# LaserProtection_Top_V10.net
KiCad netlist of a schematic drawn in Altium Designer
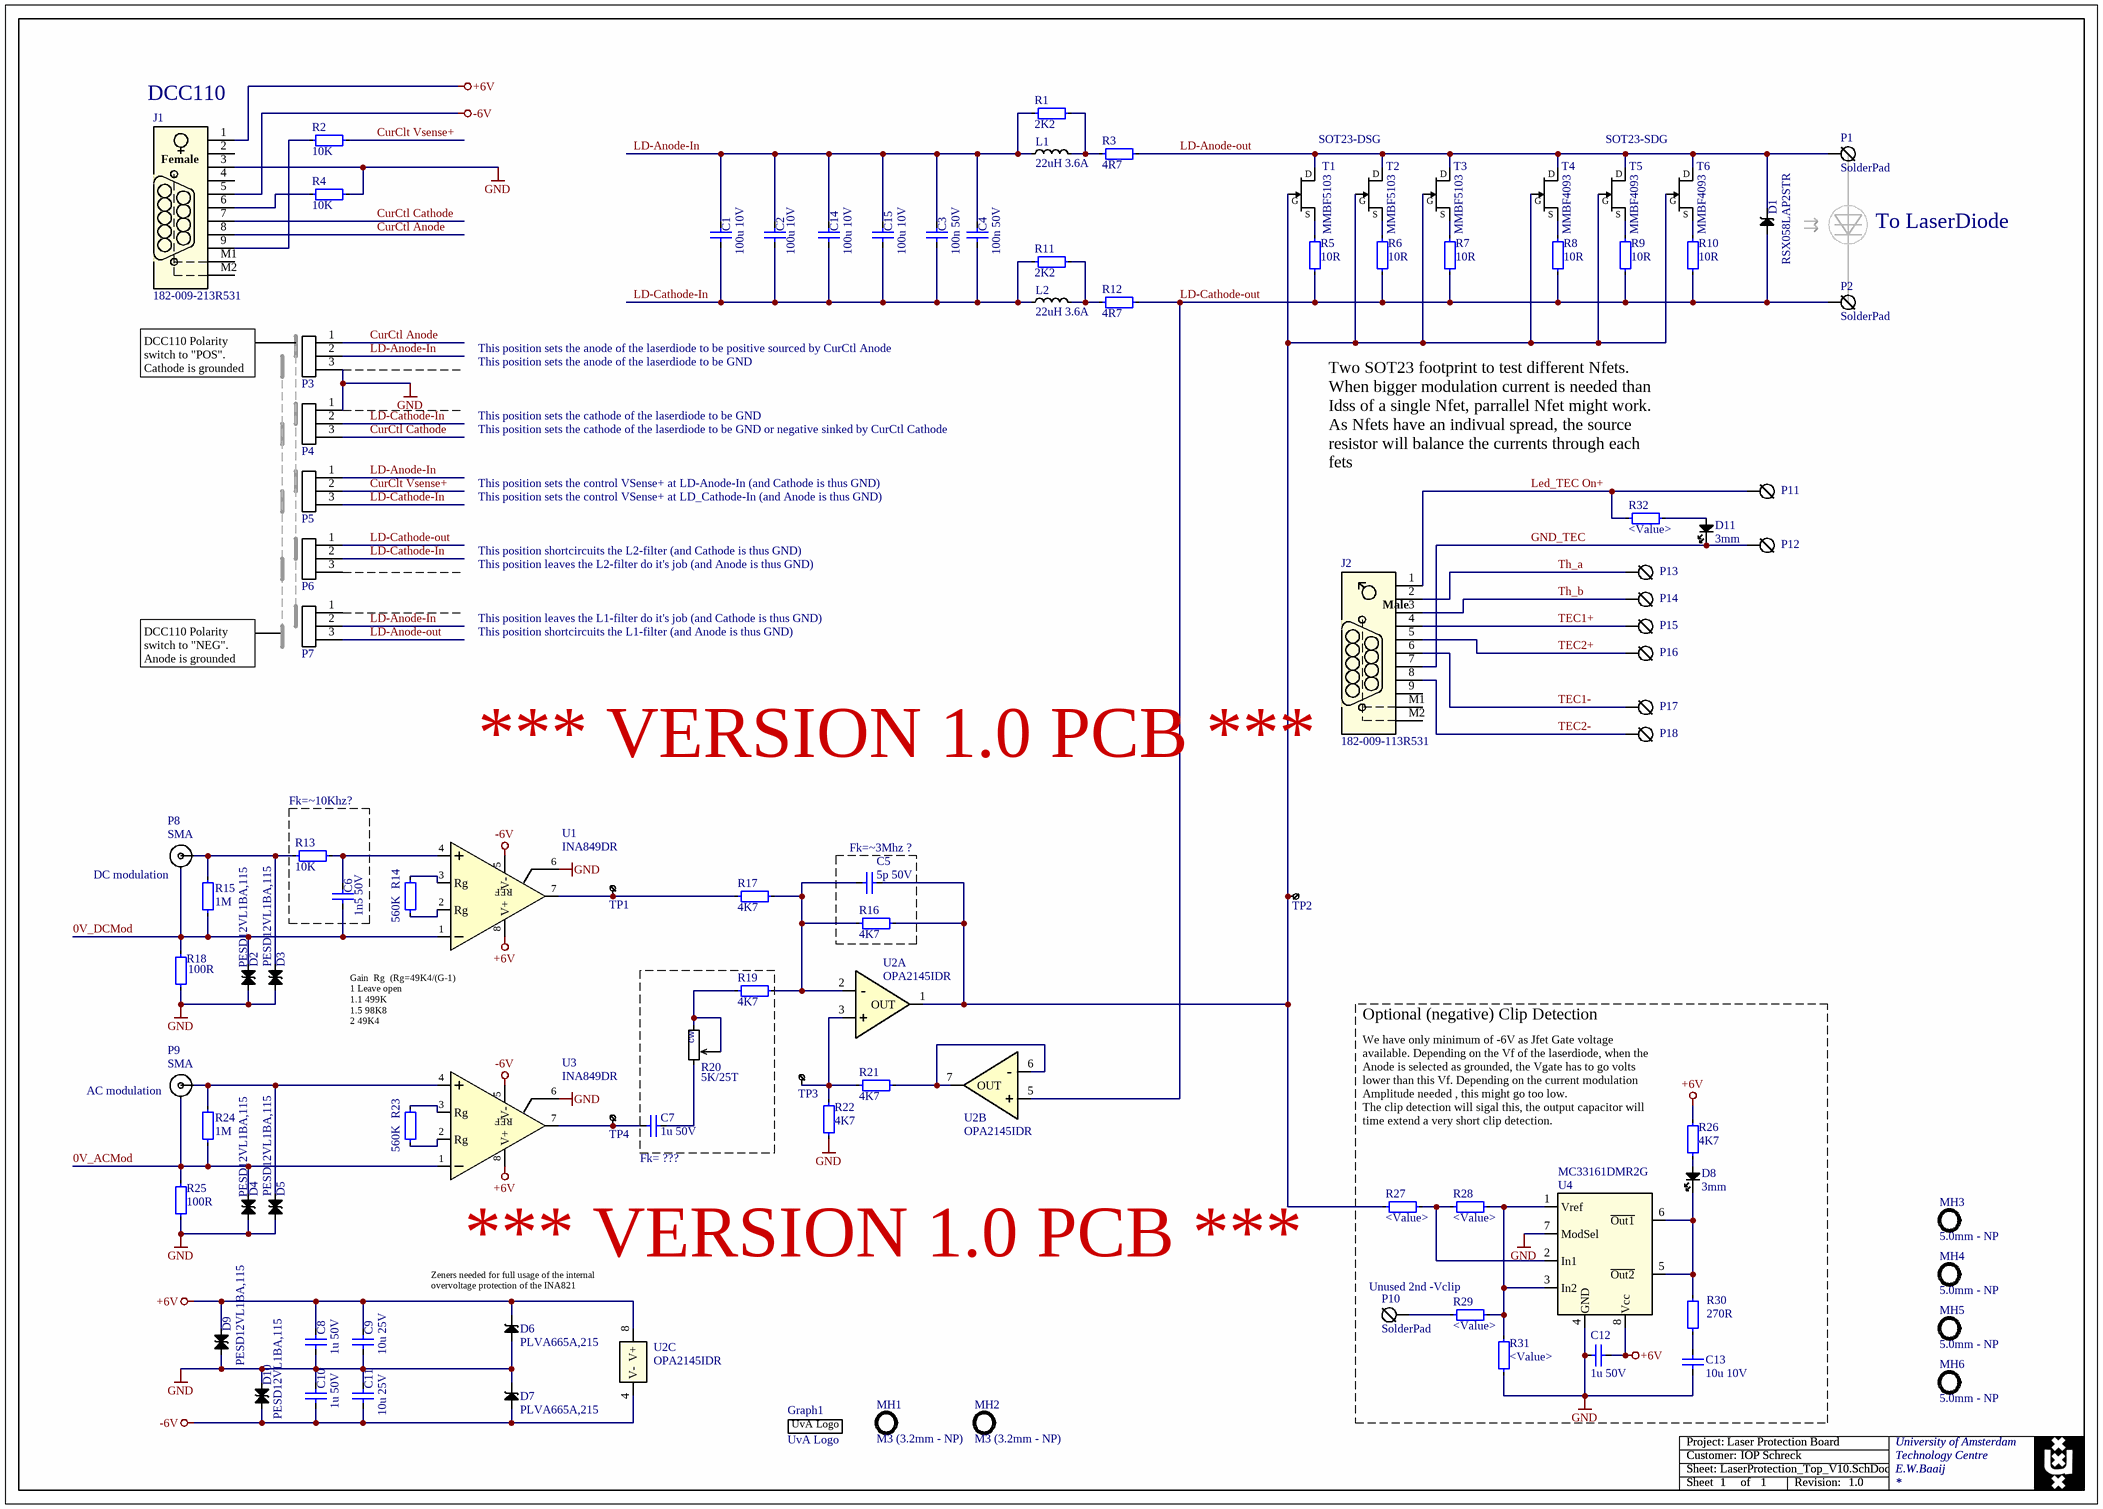
[diagram p0: LaserProtection_Top_V10.SchDoc]

(export (version "E")
  (design (tool "Eeschema 10.0.6"))
  (components
    (comp (ref "C1")
      (value "100u 10V")
      (footprint "cap1206MD")
      (description "MLCC 100 µF, 10 V, 1206 [3216 Metric], ± 20%, X5R")
      (fields
        (field (name "MANUFACTURER") "TDK")
        (field (name "AUTHOR") "EB")
        (field (name "CHECKED BY") "Unchecked")
      )
      (libsource (lib "TC_Parts") (part "capacitor"))
    )
    (comp (ref "C2")
      (value "100u 10V")
      (footprint "cap1206MD")
      (description "MLCC 100 µF, 10 V, 1206 [3216 Metric], ± 20%, X5R")
      (fields
        (field (name "MANUFACTURER") "TDK")
        (field (name "AUTHOR") "EB")
        (field (name "CHECKED BY") "Unchecked")
      )
      (libsource (lib "TC_Parts") (part "capacitor"))
    )
    (comp (ref "C3")
      (value "100n 50V")
      (footprint "cap0603MD")
      (fields
        (field (name "VOLTAGE") "50V")
        (field (name "AUTHOR") "TvR")
        (field (name "CHECKED BY") "Unchecked")
      )
      (libsource (lib "TC_Parts") (part "capacitor"))
    )
    (comp (ref "C4")
      (value "100n 50V")
      (footprint "cap0603MD")
      (fields
        (field (name "VOLTAGE") "50V")
        (field (name "AUTHOR") "TvR")
        (field (name "CHECKED BY") "Unchecked")
      )
      (libsource (lib "TC_Parts") (part "capacitor"))
    )
    (comp (ref "C5")
      (value "5p 50V")
      (footprint "cap0603MD")
      (fields
        (field (name "VOLTAGE") "50V")
        (field (name "AUTHOR") "Twe")
        (field (name "CHECKED BY") "Unchecked")
      )
      (libsource (lib "TC_Parts") (part "capacitor"))
    )
    (comp (ref "C6")
      (value "1n5 50V")
      (footprint "cap0603MD")
      (fields
        (field (name "VOLTAGE") "50V")
        (field (name "AUTHOR") "EB")
        (field (name "CHECKED BY") "Unchecked")
      )
      (libsource (lib "TC_Parts") (part "capacitor"))
    )
    (comp (ref "C7")
      (value "1u 50V")
      (footprint "cap0603MD")
      (fields
        (field (name "VOLTAGE") "50V")
        (field (name "AUTHOR") "Twe")
        (field (name "CHECKED BY") "Unchecked")
      )
      (libsource (lib "TC_Parts") (part "capacitor"))
    )
    (comp (ref "C8")
      (value "1u 50V")
      (footprint "cap0603MD")
      (fields
        (field (name "VOLTAGE") "50V")
        (field (name "AUTHOR") "Twe")
        (field (name "CHECKED BY") "Unchecked")
      )
      (libsource (lib "TC_Parts") (part "capacitor"))
    )
    (comp (ref "C9")
      (value "10u 25V")
      (footprint "cap0805MD")
      (fields
        (field (name "VOLTAGE") "25V")
        (field (name "AUTHOR") "EB")
        (field (name "CHECKED BY") "Unchecked")
      )
      (libsource (lib "TC_Parts") (part "capacitor"))
    )
    (comp (ref "C10")
      (value "1u 50V")
      (footprint "cap0603MD")
      (fields
        (field (name "VOLTAGE") "50V")
        (field (name "AUTHOR") "Twe")
        (field (name "CHECKED BY") "Unchecked")
      )
      (libsource (lib "TC_Parts") (part "capacitor"))
    )
    (comp (ref "C11")
      (value "10u 25V")
      (footprint "cap0805MD")
      (fields
        (field (name "VOLTAGE") "25V")
        (field (name "AUTHOR") "EB")
        (field (name "CHECKED BY") "Unchecked")
      )
      (libsource (lib "TC_Parts") (part "capacitor"))
    )
    (comp (ref "C12")
      (value "1u 50V")
      (footprint "cap0603MD")
      (fields
        (field (name "VOLTAGE") "50V")
        (field (name "AUTHOR") "Twe")
        (field (name "CHECKED BY") "Unchecked")
      )
      (libsource (lib "TC_Parts") (part "capacitor"))
    )
    (comp (ref "C13")
      (value "10u 10V")
      (footprint "cap0603MD")
      (fields
        (field (name "VOLTAGE") "10V")
        (field (name "AUTHOR") "EB")
        (field (name "CHECKED BY") "Unchecked")
      )
      (libsource (lib "TC_Parts") (part "capacitor"))
    )
    (comp (ref "C14")
      (value "100u 10V")
      (footprint "cap1206MD")
      (description "MLCC 100 µF, 10 V, 1206 [3216 Metric], ± 20%, X5R")
      (fields
        (field (name "MANUFACTURER") "TDK")
        (field (name "AUTHOR") "EB")
        (field (name "CHECKED BY") "Unchecked")
      )
      (libsource (lib "TC_Parts") (part "capacitor"))
    )
    (comp (ref "C15")
      (value "100u 10V")
      (footprint "cap1206MD")
      (description "MLCC 100 µF, 10 V, 1206 [3216 Metric], ± 20%, X5R")
      (fields
        (field (name "MANUFACTURER") "TDK")
        (field (name "AUTHOR") "EB")
        (field (name "CHECKED BY") "Unchecked")
      )
      (libsource (lib "TC_Parts") (part "capacitor"))
    )
    (comp (ref "D1")
      (value "RSX058LAP2STR")
      (footprint "SODFL470X110-2N")
      (description "Schottky Diode, 3A, 200V, Vf=0.84 (3A/35C), Ir=5-100nA")
      (fields
        (field (name "MANUFACTURER") "ROHM")
        (field (name "AUTHOR") "EB")
        (field (name "CHECKED BY") "Unchecked")
      )
      (libsource (lib "TC_Parts") (part "DIODEZENER_CA"))
    )
    (comp (ref "D2")
      (value "PESD12VL1BA,115")
      (footprint "SOD-323-2-NoPol")
      (description "TVS Diode, Bidirectional, 12V, SOD-323, 2 Pins")
      (fields
        (field (name "MANUFACTURER") "Nexperia")
        (field (name "AUTHOR") "EB")
        (field (name "CHECKED BY") "Unchecked")
      )
      (libsource (lib "TC_Parts") (part "diodeSuppressor"))
    )
    (comp (ref "D3")
      (value "PESD12VL1BA,115")
      (footprint "SOD-323-2-NoPol")
      (description "TVS Diode, Bidirectional, 12V, SOD-323, 2 Pins")
      (fields
        (field (name "MANUFACTURER") "Nexperia")
        (field (name "AUTHOR") "EB")
        (field (name "CHECKED BY") "Unchecked")
      )
      (libsource (lib "TC_Parts") (part "diodeSuppressor"))
    )
    (comp (ref "D4")
      (value "PESD12VL1BA,115")
      (footprint "SOD-323-2-NoPol")
      (description "TVS Diode, Bidirectional, 12V, SOD-323, 2 Pins")
      (fields
        (field (name "MANUFACTURER") "Nexperia")
        (field (name "AUTHOR") "EB")
        (field (name "CHECKED BY") "Unchecked")
      )
      (libsource (lib "TC_Parts") (part "diodeSuppressor"))
    )
    (comp (ref "D5")
      (value "PESD12VL1BA,115")
      (footprint "SOD-323-2-NoPol")
      (description "TVS Diode, Bidirectional, 12V, SOD-323, 2 Pins")
      (fields
        (field (name "MANUFACTURER") "Nexperia")
        (field (name "AUTHOR") "EB")
        (field (name "CHECKED BY") "Unchecked")
      )
      (libsource (lib "TC_Parts") (part "diodeSuppressor"))
    )
    (comp (ref "D6")
      (value "PLVA665A,215")
      (footprint "SOT95P230X110-3N")
      (description "Zener 6v5, 250mW, 3%, SOT-23")
      (fields
        (field (name "MANUFACTURER") "Rohm")
        (field (name "AUTHOR") "EB")
        (field (name "CHECKED BY") "Unchecked")
      )
      (libsource (lib "TC_Parts") (part "DIODEZENER_AxC"))
    )
    (comp (ref "D7")
      (value "PLVA665A,215")
      (footprint "SOT95P230X110-3N")
      (description "Zener 6v5, 250mW, 3%, SOT-23")
      (fields
        (field (name "MANUFACTURER") "Rohm")
        (field (name "AUTHOR") "EB")
        (field (name "CHECKED BY") "Unchecked")
      )
      (libsource (lib "TC_Parts") (part "DIODEZENER_AxC"))
    )
    (comp (ref "D8")
      (value "3mm")
      (footprint "LED_3mm")
      (description "Generic 3mm LED Footprint")
      (fields
        (field (name "MANUFACTURER") "Wurth")
        (field (name "AUTHOR") "EB")
        (field (name "CHECKED BY") "Unchecked")
      )
      (libsource (lib "TC_Parts") (part "LED_CA"))
    )
    (comp (ref "D9")
      (value "PESD12VL1BA,115")
      (footprint "SOD-323-2-NoPol")
      (description "TVS Diode, Bidirectional, 12V, SOD-323, 2 Pins")
      (fields
        (field (name "MANUFACTURER") "Nexperia")
        (field (name "AUTHOR") "EB")
        (field (name "CHECKED BY") "Unchecked")
      )
      (libsource (lib "TC_Parts") (part "diodeSuppressor"))
    )
    (comp (ref "D10")
      (value "PESD12VL1BA,115")
      (footprint "SOD-323-2-NoPol")
      (description "TVS Diode, Bidirectional, 12V, SOD-323, 2 Pins")
      (fields
        (field (name "MANUFACTURER") "Nexperia")
        (field (name "AUTHOR") "EB")
        (field (name "CHECKED BY") "Unchecked")
      )
      (libsource (lib "TC_Parts") (part "diodeSuppressor"))
    )
    (comp (ref "D11")
      (value "3mm")
      (footprint "LED_3mm")
      (description "Generic 3mm LED Footprint")
      (fields
        (field (name "MANUFACTURER") "Wurth")
        (field (name "AUTHOR") "EB")
        (field (name "CHECKED BY") "Unchecked")
      )
      (libsource (lib "TC_Parts") (part "LED_CA"))
    )
    (comp (ref "Graph1")
      (value "UvA Logo")
      (footprint "UVA_LOGO_SMALL_HOR")
      (description "University of Amsterdam Logo")
      (fields (field (name "AUTHOR") "EB") (field (name "CHECKED BY") "PCB"))
      (libsource (lib "TC_Parts") (part "UvA_Logo"))
    )
    (comp (ref "J1")
      (value "182-009-213R531")
      (footprint "182-009-213Ryy1")
      (description "NorComp, D-SUB, 9 pins, Female, right angled PCB")
      (fields
        (field (name "MANUFACTURER") "NorComp")
        (field (name "AUTHOR") "EB")
        (field (name "CHECKED BY") "Unchecked")
      )
      (libsource (lib "TC_Parts") (part "D-SUB_9p_Female_PCB"))
    )
    (comp (ref "J2")
      (value "182-009-113R531")
      (footprint "182-009-113Ryy1")
      (description "NorComp, D-SUB, 9 pins, Male, right angled PCB")
      (fields
        (field (name "MANUFACTURER") "NorComp")
        (field (name "AUTHOR") "EB")
        (field (name "CHECKED BY") "Unchecked")
      )
      (libsource (lib "TC_Parts") (part "D-SUB_9p_Male_PCB"))
    )
    (comp (ref "L1")
      (value "22uH 3.6A")
      (footprint "INDP102100X51N")
      (description "Power Inductor, SMD, 22 µH, 3.58 A, Shielded, 2.36 A")
      (fields
        (field (name "MANUFACTURER") "Coilcraft")
        (field (name "AUTHOR") "EB")
        (field (name "CHECKED BY") "Unchecked")
      )
      (libsource (lib "TC_Parts") (part "coil"))
    )
    (comp (ref "L2")
      (value "22uH 3.6A")
      (footprint "INDP102100X51N")
      (description "Power Inductor, SMD, 22 µH, 3.58 A, Shielded, 2.36 A")
      (fields
        (field (name "MANUFACTURER") "Coilcraft")
        (field (name "AUTHOR") "EB")
        (field (name "CHECKED BY") "Unchecked")
      )
      (libsource (lib "TC_Parts") (part "coil"))
    )
    (comp (ref "MH1")
      (value "M3 (3.2mm - NP)")
      (footprint "MountHole M3 NP keepout 6_5mm")
      (description "MountingHole NP for M3, drill 3.2mm, keepout dia 6.5")
      (fields (field (name "AUTHOR") "EB") (field (name "CHECKED BY") "Unchecked"))
      (libsource (lib "TC_Parts") (part "MountHole_NP"))
    )
    (comp (ref "MH2")
      (value "M3 (3.2mm - NP)")
      (footprint "MountHole M3 NP keepout 6_5mm")
      (description "MountingHole NP for M3, drill 3.2mm, keepout dia 6.5")
      (fields (field (name "AUTHOR") "EB") (field (name "CHECKED BY") "Unchecked"))
      (libsource (lib "TC_Parts") (part "MountHole_NP"))
    )
    (comp (ref "MH3")
      (value "5.0mm - NP")
      (footprint "MountHole 5mm NP No keepout")
      (description "MountingHole 5mm No keepout")
      (fields (field (name "AUTHOR") "EB") (field (name "CHECKED BY") "Unchecked"))
      (libsource (lib "TC_Parts") (part "MountHole_NP"))
    )
    (comp (ref "MH4")
      (value "5.0mm - NP")
      (footprint "MountHole 5mm NP No keepout")
      (description "MountingHole 5mm No keepout")
      (fields (field (name "AUTHOR") "EB") (field (name "CHECKED BY") "Unchecked"))
      (libsource (lib "TC_Parts") (part "MountHole_NP"))
    )
    (comp (ref "MH5")
      (value "5.0mm - NP")
      (footprint "MountHole 5mm NP No keepout")
      (description "MountingHole 5mm No keepout")
      (fields (field (name "AUTHOR") "EB") (field (name "CHECKED BY") "Unchecked"))
      (libsource (lib "TC_Parts") (part "MountHole_NP"))
    )
    (comp (ref "MH6")
      (value "5.0mm - NP")
      (footprint "MountHole 5mm NP No keepout")
      (description "MountingHole 5mm No keepout")
      (fields (field (name "AUTHOR") "EB") (field (name "CHECKED BY") "Unchecked"))
      (libsource (lib "TC_Parts") (part "MountHole_NP"))
    )
    (comp (ref "P1")
      (value "SolderPad")
      (footprint "Pad_PT_c15h07mm")
      (description "SolderPad_PT_c1.5h0.7mm")
      (fields (field (name "AUTHOR") "EB") (field (name "CHECKED BY") "Unchecked"))
      (libsource (lib "TC_Parts") (part "SolderPad"))
    )
    (comp (ref "P2")
      (value "SolderPad")
      (footprint "Pad_PT_c15h07mm")
      (description "SolderPad_PT_c1.5h0.7mm")
      (fields (field (name "AUTHOR") "EB") (field (name "CHECKED BY") "Unchecked"))
      (libsource (lib "TC_Parts") (part "SolderPad"))
    )
    (comp (ref "P3")
      (value "Header 2.54")
      (footprint "Header254-1x3")
      (description "Header 2.54p 1x3")
      (fields (field (name "AUTHOR") "Twe") (field (name "CHECKED BY") "PCB"))
      (libsource (lib "TC_Parts") (part "header1x3"))
    )
    (comp (ref "P4")
      (value "Header 2.54")
      (footprint "Header254-1x3")
      (description "Header 2.54p 1x3")
      (fields (field (name "AUTHOR") "Twe") (field (name "CHECKED BY") "PCB"))
      (libsource (lib "TC_Parts") (part "header1x3"))
    )
    (comp (ref "P5")
      (value "Header 2.54")
      (footprint "Header254-1x3")
      (description "Header 2.54p 1x3")
      (fields (field (name "AUTHOR") "Twe") (field (name "CHECKED BY") "PCB"))
      (libsource (lib "TC_Parts") (part "header1x3"))
    )
    (comp (ref "P6")
      (value "Header 2.54")
      (footprint "Header254-1x3")
      (description "Header 2.54p 1x3")
      (fields (field (name "AUTHOR") "Twe") (field (name "CHECKED BY") "PCB"))
      (libsource (lib "TC_Parts") (part "header1x3"))
    )
    (comp (ref "P7")
      (value "Header 2.54")
      (footprint "Header254-1x3")
      (description "Header 2.54p 1x3")
      (fields (field (name "AUTHOR") "Twe") (field (name "CHECKED BY") "PCB"))
      (libsource (lib "TC_Parts") (part "header1x3"))
    )
    (comp (ref "P8")
      (value "SMA")
      (footprint "PCB114SMAFSTJ")
      (description "SMA Coaxial, 17.7mm, 50 Ohm, Straight Jack, Through Hole")
      (fields
        (field (name "MANUFACTURER") "Taoglas")
        (field (name "AUTHOR") "EB")
        (field (name "CHECKED BY") "Unchecked")
      )
      (libsource (lib "TC_Parts") (part "SMA"))
    )
    (comp (ref "P9")
      (value "SMA")
      (footprint "PCB114SMAFSTJ")
      (description "SMA Coaxial, 17.7mm, 50 Ohm, Straight Jack, Through Hole")
      (fields
        (field (name "MANUFACTURER") "Taoglas")
        (field (name "AUTHOR") "EB")
        (field (name "CHECKED BY") "Unchecked")
      )
      (libsource (lib "TC_Parts") (part "SMA"))
    )
    (comp (ref "P10")
      (value "SolderPad")
      (footprint "Pad_SMD_c20mm")
      (description "SolderPad_SMD_c2.0mm")
      (fields (field (name "AUTHOR") "EB") (field (name "CHECKED BY") "Unchecked"))
      (libsource (lib "TC_Parts") (part "SolderPad"))
    )
    (comp (ref "P11")
      (value "SolderPad")
      (footprint "Pad_PT_c16h08mm")
      (description "SolderPad_PT_c1.6h0.8mm")
      (fields (field (name "AUTHOR") "EB") (field (name "CHECKED BY") "Unchecked"))
      (libsource (lib "TC_Parts") (part "SolderPad"))
    )
    (comp (ref "P12")
      (value "SolderPad")
      (footprint "Pad_PT_c16h08mm")
      (description "SolderPad_PT_c1.6h0.8mm")
      (fields (field (name "AUTHOR") "EB") (field (name "CHECKED BY") "Unchecked"))
      (libsource (lib "TC_Parts") (part "SolderPad"))
    )
    (comp (ref "P13")
      (value "SolderPad")
      (footprint "Pad_PT_c16h08mm")
      (description "SolderPad_PT_c1.6h0.8mm")
      (fields (field (name "AUTHOR") "EB") (field (name "CHECKED BY") "Unchecked"))
      (libsource (lib "TC_Parts") (part "SolderPad"))
    )
    (comp (ref "P14")
      (value "SolderPad")
      (footprint "Pad_PT_c16h08mm")
      (description "SolderPad_PT_c1.6h0.8mm")
      (fields (field (name "AUTHOR") "EB") (field (name "CHECKED BY") "Unchecked"))
      (libsource (lib "TC_Parts") (part "SolderPad"))
    )
    (comp (ref "P15")
      (value "SolderPad")
      (footprint "Pad_PT_c20h10mm")
      (description "SolderPad_PT_c2.0h1.0mm")
      (fields (field (name "AUTHOR") "EB") (field (name "CHECKED BY") "Unchecked"))
      (libsource (lib "TC_Parts") (part "SolderPad"))
    )
    (comp (ref "P16")
      (value "SolderPad")
      (footprint "Pad_PT_c20h10mm")
      (description "SolderPad_PT_c2.0h1.0mm")
      (fields (field (name "AUTHOR") "EB") (field (name "CHECKED BY") "Unchecked"))
      (libsource (lib "TC_Parts") (part "SolderPad"))
    )
    (comp (ref "P17")
      (value "SolderPad")
      (footprint "Pad_PT_c20h10mm")
      (description "SolderPad_PT_c2.0h1.0mm")
      (fields (field (name "AUTHOR") "EB") (field (name "CHECKED BY") "Unchecked"))
      (libsource (lib "TC_Parts") (part "SolderPad"))
    )
    (comp (ref "P18")
      (value "SolderPad")
      (footprint "Pad_PT_c20h10mm")
      (description "SolderPad_PT_c2.0h1.0mm")
      (fields (field (name "AUTHOR") "EB") (field (name "CHECKED BY") "Unchecked"))
      (libsource (lib "TC_Parts") (part "SolderPad"))
    )
    (comp (ref "R1")
      (value "2K2")
      (footprint "res1206MD")
      (fields (field (name "AUTHOR") "EB") (field (name "CHECKED BY") "Unchecked"))
      (libsource (lib "") (part "resistor_1"))
    )
    (comp (ref "R2")
      (value "10K")
      (footprint "res0603MD")
      (fields (field (name "AUTHOR") "TvR") (field (name "CHECKED BY") "Unchecked"))
      (libsource (lib "") (part "resistor_1"))
    )
    (comp (ref "R3")
      (value "4R7")
      (footprint "RES2512MD")
      (description "SMD Chip Resistor, 4.7 ohm, ± 5%, 2 W, 2512")
      (fields
        (field (name "MANUFACTURER") "Yageo")
        (field (name "AUTHOR") "EB")
        (field (name "CHECKED BY") "Unchecked")
      )
      (libsource (lib "") (part "resistor_1"))
    )
    (comp (ref "R4")
      (value "10K")
      (footprint "res0603MD")
      (fields (field (name "AUTHOR") "TvR") (field (name "CHECKED BY") "Unchecked"))
      (libsource (lib "") (part "resistor_1"))
    )
    (comp (ref "R5")
      (value "10R")
      (footprint "res0603MD")
      (fields (field (name "AUTHOR") "Twe") (field (name "CHECKED BY") "Unchecked"))
      (libsource (lib "TC_Parts") (part "resistor"))
    )
    (comp (ref "R6")
      (value "10R")
      (footprint "res0603MD")
      (fields (field (name "AUTHOR") "Twe") (field (name "CHECKED BY") "Unchecked"))
      (libsource (lib "TC_Parts") (part "resistor"))
    )
    (comp (ref "R7")
      (value "10R")
      (footprint "res0603MD")
      (fields (field (name "AUTHOR") "Twe") (field (name "CHECKED BY") "Unchecked"))
      (libsource (lib "TC_Parts") (part "resistor"))
    )
    (comp (ref "R8")
      (value "10R")
      (footprint "res0603MD")
      (fields (field (name "AUTHOR") "Twe") (field (name "CHECKED BY") "Unchecked"))
      (libsource (lib "TC_Parts") (part "resistor"))
    )
    (comp (ref "R9")
      (value "10R")
      (footprint "res0603MD")
      (fields (field (name "AUTHOR") "Twe") (field (name "CHECKED BY") "Unchecked"))
      (libsource (lib "TC_Parts") (part "resistor"))
    )
    (comp (ref "R10")
      (value "10R")
      (footprint "res0603MD")
      (fields (field (name "AUTHOR") "Twe") (field (name "CHECKED BY") "Unchecked"))
      (libsource (lib "TC_Parts") (part "resistor"))
    )
    (comp (ref "R11")
      (value "2K2")
      (footprint "res1206MD")
      (fields (field (name "AUTHOR") "EB") (field (name "CHECKED BY") "Unchecked"))
      (libsource (lib "") (part "resistor_1"))
    )
    (comp (ref "R12")
      (value "4R7")
      (footprint "RES2512MD")
      (description "SMD Chip Resistor, 4.7 ohm, ± 5%, 2 W, 2512")
      (fields
        (field (name "MANUFACTURER") "Yageo")
        (field (name "AUTHOR") "EB")
        (field (name "CHECKED BY") "Unchecked")
      )
      (libsource (lib "") (part "resistor_1"))
    )
    (comp (ref "R13")
      (value "10K")
      (footprint "res0603MD")
      (fields (field (name "AUTHOR") "TvR") (field (name "CHECKED BY") "Unchecked"))
      (libsource (lib "") (part "resistor_1"))
    )
    (comp (ref "R14")
      (value "560K")
      (footprint "res0603MD")
      (fields (field (name "AUTHOR") "Twe") (field (name "CHECKED BY") "Unchecked"))
      (libsource (lib "") (part "resistor_1"))
    )
    (comp (ref "R15")
      (value "1M")
      (footprint "res0603MD")
      (fields (field (name "AUTHOR") "Twe") (field (name "CHECKED BY") "Unchecked"))
      (libsource (lib "TC_Parts") (part "resistor"))
    )
    (comp (ref "R16")
      (value "4K7")
      (footprint "res0603MD")
      (fields (field (name "AUTHOR") "Twe") (field (name "CHECKED BY") "Unchecked"))
      (libsource (lib "") (part "resistor_1"))
    )
    (comp (ref "R17")
      (value "4K7")
      (footprint "res0603MD")
      (fields (field (name "AUTHOR") "Twe") (field (name "CHECKED BY") "Unchecked"))
      (libsource (lib "") (part "resistor_1"))
    )
    (comp (ref "R18")
      (value "100R")
      (footprint "res0603MD")
      (fields (field (name "AUTHOR") "TvR") (field (name "CHECKED BY") "Unchecked"))
      (libsource (lib "TC_Parts") (part "resistor"))
    )
    (comp (ref "R19")
      (value "4K7")
      (footprint "res0603MD")
      (fields (field (name "AUTHOR") "Twe") (field (name "CHECKED BY") "Unchecked"))
      (libsource (lib "") (part "resistor_1"))
    )
    (comp (ref "R20")
      (value "5K/25T")
      (footprint "Bourns 3296Y")
      (description "5K, 25 Turn, Top adjust thruhole trimpot Bourns 100pm")
      (fields
        (field (name "MANUFACTURER") "Bourns")
        (field (name "AUTHOR") "EB")
        (field (name "CHECKED BY") "Unchecked")
      )
      (libsource (lib "TC_Parts") (part "TRIMPOT"))
    )
    (comp (ref "R21")
      (value "4K7")
      (footprint "res0603MD")
      (fields (field (name "AUTHOR") "Twe") (field (name "CHECKED BY") "Unchecked"))
      (libsource (lib "") (part "resistor_2"))
    )
    (comp (ref "R22")
      (value "4K7")
      (footprint "res0603MD")
      (fields (field (name "AUTHOR") "Twe") (field (name "CHECKED BY") "Unchecked"))
      (libsource (lib "TC_Parts") (part "resistor"))
    )
    (comp (ref "R23")
      (value "560K")
      (footprint "res0603MD")
      (fields (field (name "AUTHOR") "Twe") (field (name "CHECKED BY") "Unchecked"))
      (libsource (lib "") (part "resistor_1"))
    )
    (comp (ref "R24")
      (value "1M")
      (footprint "res0603MD")
      (fields (field (name "AUTHOR") "Twe") (field (name "CHECKED BY") "Unchecked"))
      (libsource (lib "TC_Parts") (part "resistor"))
    )
    (comp (ref "R25")
      (value "100R")
      (footprint "res0603MD")
      (fields (field (name "AUTHOR") "TvR") (field (name "CHECKED BY") "Unchecked"))
      (libsource (lib "TC_Parts") (part "resistor"))
    )
    (comp (ref "R26")
      (value "4K7")
      (footprint "res0603MD")
      (fields (field (name "AUTHOR") "Twe") (field (name "CHECKED BY") "Unchecked"))
      (libsource (lib "") (part "resistor_3"))
    )
    (comp (ref "R27")
      (value "<Value>")
      (footprint "res0603MD")
      (fields (field (name "AUTHOR") "Twe") (field (name "CHECKED BY") "Unchecked"))
      (libsource (lib "") (part "resistor_1"))
    )
    (comp (ref "R28")
      (value "<Value>")
      (footprint "res0603MD")
      (fields (field (name "AUTHOR") "Twe") (field (name "CHECKED BY") "Unchecked"))
      (libsource (lib "") (part "resistor_1"))
    )
    (comp (ref "R29")
      (value "<Value>")
      (footprint "res0603MD")
      (fields (field (name "AUTHOR") "Twe") (field (name "CHECKED BY") "Unchecked"))
      (libsource (lib "") (part "resistor_1"))
    )
    (comp (ref "R30")
      (value "270R")
      (footprint "res0603MD")
      (fields (field (name "AUTHOR") "Twe") (field (name "CHECKED BY") "Unchecked"))
      (libsource (lib "TC_Parts") (part "resistor"))
    )
    (comp (ref "R31")
      (value "<Value>")
      (footprint "res0603MD")
      (fields (field (name "AUTHOR") "Twe") (field (name "CHECKED BY") "Unchecked"))
      (libsource (lib "") (part "resistor_3"))
    )
    (comp (ref "R32")
      (value "<Value>")
      (footprint "res0805HD")
      (fields (field (name "AUTHOR") "Twe") (field (name "CHECKED BY") "Unchecked"))
      (libsource (lib "") (part "resistor_1"))
    )
    (comp (ref "T1")
      (value "MMBF5103")
      (footprint "SOT95P230X110-3N")
      (description "JFET N Channel, VdgMax=40V, Idss=10 to 40mA, VgsOff=-1.2 to-2.7 V, SOT-23-3")
      (fields
        (field (name "MANUFACTURER") "OnSemi")
        (field (name "AUTHOR") "EB")
        (field (name "CHECKED BY") "Unchecked")
      )
      (libsource (lib "TC_Parts") (part "JFET-N_DSG"))
    )
    (comp (ref "T2")
      (value "MMBF5103")
      (footprint "SOT95P230X110-3N")
      (description "JFET N Channel, VdgMax=40V, Idss=10 to 40mA, VgsOff=-1.2 to-2.7 V, SOT-23-3")
      (fields
        (field (name "MANUFACTURER") "OnSemi")
        (field (name "AUTHOR") "EB")
        (field (name "CHECKED BY") "Unchecked")
      )
      (libsource (lib "TC_Parts") (part "JFET-N_DSG"))
    )
    (comp (ref "T3")
      (value "MMBF5103")
      (footprint "SOT95P230X110-3N")
      (description "JFET N Channel, VdgMax=40V, Idss=10 to 40mA, VgsOff=-1.2 to-2.7 V, SOT-23-3")
      (fields
        (field (name "MANUFACTURER") "OnSemi")
        (field (name "AUTHOR") "EB")
        (field (name "CHECKED BY") "Unchecked")
      )
      (libsource (lib "TC_Parts") (part "JFET-N_DSG"))
    )
    (comp (ref "T4")
      (value "MMBF4093")
      (footprint "SOT95P230X110-3N")
      (description "JFET N Channel, VdgMax=40V, Idss=8 to ?mA, VgsOff=-1 to -5V, SOT-23-3")
      (fields
        (field (name "MANUFACTURER") "OnSemi")
        (field (name "AUTHOR") "EB")
        (field (name "CHECKED BY") "Unchecked")
      )
      (libsource (lib "TC_Parts") (part "JFET-N_SDG"))
    )
    (comp (ref "T5")
      (value "MMBF4093")
      (footprint "SOT95P230X110-3N")
      (description "JFET N Channel, VdgMax=40V, Idss=8 to ?mA, VgsOff=-1 to -5V, SOT-23-3")
      (fields
        (field (name "MANUFACTURER") "OnSemi")
        (field (name "AUTHOR") "EB")
        (field (name "CHECKED BY") "Unchecked")
      )
      (libsource (lib "TC_Parts") (part "JFET-N_SDG"))
    )
    (comp (ref "T6")
      (value "MMBF4093")
      (footprint "SOT95P230X110-3N")
      (description "JFET N Channel, VdgMax=40V, Idss=8 to ?mA, VgsOff=-1 to -5V, SOT-23-3")
      (fields
        (field (name "MANUFACTURER") "OnSemi")
        (field (name "AUTHOR") "EB")
        (field (name "CHECKED BY") "Unchecked")
      )
      (libsource (lib "TC_Parts") (part "JFET-N_SDG"))
    )
    (comp (ref "TP1")
      (value "Testpoint")
      (footprint "Testpoint_1mm5")
      (description "Testpoint SMD pad 1.5mm")
      (fields (field (name "AUTHOR") "EB") (field (name "CHECKED BY") "PCB"))
      (libsource (lib "TC_Parts") (part "testpoint"))
    )
    (comp (ref "TP2")
      (value "Testpoint")
      (footprint "Testpoint_1mm5")
      (description "Testpoint SMD pad 1.5mm")
      (fields (field (name "AUTHOR") "EB") (field (name "CHECKED BY") "PCB"))
      (libsource (lib "TC_Parts") (part "testpoint"))
    )
    (comp (ref "TP3")
      (value "Testpoint")
      (footprint "Testpoint_1mm5")
      (description "Testpoint SMD pad 1.5mm")
      (fields (field (name "AUTHOR") "EB") (field (name "CHECKED BY") "PCB"))
      (libsource (lib "TC_Parts") (part "testpoint"))
    )
    (comp (ref "TP4")
      (value "Testpoint")
      (footprint "Testpoint_1mm5")
      (description "Testpoint SMD pad 1.5mm")
      (fields (field (name "AUTHOR") "EB") (field (name "CHECKED BY") "PCB"))
      (libsource (lib "TC_Parts") (part "testpoint"))
    )
    (comp (ref "U1")
      (value "INA849DR")
      (footprint "SOIC127P600X175-8N")
      (description "InAmp, noise=1 nV/√Hz, Ofs=35 µV, Bw=28MHz-35V/us, ± 4V to ± 18V, 8V to 36V")
      (fields
        (field (name "MANUFACTURER") "Anolog Devices")
        (field (name "AUTHOR") "EB")
        (field (name "CHECKED BY") "Unchecked")
      )
      (libsource (lib "TC_Parts") (part "INA849D"))
    )
    (comp (ref "U2")
      (value "OPA2145IDR")
      (footprint "SOIC127P600X175-8N")
      (description "Dual OpAmp, 5.5MHz, Noise=7nV, Ibias=2pA, ±2.3 to ±18v, UnityGain stable, Sot23-5")
      (fields
        (field (name "MANUFACTURER") "Analog Devices")
        (field (name "AUTHOR") "EB")
        (field (name "CHECKED BY") "Unchecked")
      )
      (libsource (lib "TC_Parts") (part "OPA2145IDR"))
    )
    (comp (ref "U3")
      (value "INA849DR")
      (footprint "SOIC127P600X175-8N")
      (description "InAmp, noise=1 nV/√Hz, Ofs=35 µV, Bw=28MHz-35V/us, ± 4V to ± 18V, 8V to 36V")
      (fields
        (field (name "MANUFACTURER") "Anolog Devices")
        (field (name "AUTHOR") "EB")
        (field (name "CHECKED BY") "Unchecked")
      )
      (libsource (lib "TC_Parts") (part "INA849D"))
    )
    (comp (ref "U4")
      (value "MC33161DMR2G")
      (footprint "TSOP65P490X110-8N")
      (description "2-40V Window Comparator, internal ref (2.54/1.27V), open collector out")
      (fields
        (field (name "MANUFACTURER") "OnSemi")
        (field (name "AUTHOR") "EB")
        (field (name "CHECKED BY") "Unchecked")
      )
      (libsource (lib "TC_Parts") (part "MC34161_MC33161_NVC33161"))
    )
  )
  (nets
    (net (code "1") (name "+6V") (class "Default")
      (node (ref "C12") (pin "1") (pinfunction "1_1") (pintype "passive"))
      (node (ref "C8") (pin "2") (pinfunction "2_2") (pintype "passive"))
      (node (ref "C9") (pin "2") (pinfunction "2_2") (pintype "passive"))
      (node (ref "D6") (pin "3") (pinfunction "C_3") (pintype "passive"))
      (node (ref "D9") (pin "2") (pinfunction "2_2") (pintype "passive"))
      (node (ref "J1") (pin "1") (pintype "passive"))
      (node (ref "R26") (pin "1") (pinfunction "1_1") (pintype "passive"))
      (node (ref "U1") (pin "8") (pinfunction "V+_8") (pintype "passive"))
      (node (ref "U2") (pin "8") (pinfunction "V+_8") (pintype "passive"))
      (node (ref "U3") (pin "8") (pinfunction "V+_8") (pintype "passive"))
      (node (ref "U4") (pin "8") (pinfunction "Vcc_8") (pintype "passive"))
    )
    (net (code "2") (name "-6V") (class "Default")
      (node (ref "C10") (pin "1") (pinfunction "1_1") (pintype "passive"))
      (node (ref "C11") (pin "1") (pinfunction "1_1") (pintype "passive"))
      (node (ref "D10") (pin "1") (pinfunction "1_1") (pintype "passive"))
      (node (ref "D7") (pin "1") (pinfunction "A_1") (pintype "passive"))
      (node (ref "J1") (pin "5") (pintype "passive"))
      (node (ref "U1") (pin "5") (pinfunction "V-_5") (pintype "passive"))
      (node (ref "U2") (pin "4") (pinfunction "V-_4") (pintype "passive"))
      (node (ref "U3") (pin "5") (pinfunction "V-_5") (pintype "passive"))
    )
    (net (code "3") (name "/0V_ACMod") (class "Default")
      (node (ref "D4") (pin "2") (pinfunction "2_2") (pintype "passive"))
      (node (ref "P9") (pin "2") (pinfunction "2_2") (pintype "passive"))
      (node (ref "R24") (pin "1") (pinfunction "1_1") (pintype "passive"))
      (node (ref "R25") (pin "2") (pinfunction "2_2") (pintype "passive"))
      (node (ref "U3") (pin "1") (pinfunction "-_1") (pintype "passive"))
    )
    (net (code "4") (name "/0V_DCMod") (class "Default")
      (node (ref "C6") (pin "2") (pinfunction "2_2") (pintype "passive"))
      (node (ref "D2") (pin "2") (pinfunction "2_2") (pintype "passive"))
      (node (ref "P8") (pin "2") (pinfunction "2_2") (pintype "passive"))
      (node (ref "R15") (pin "1") (pinfunction "1_1") (pintype "passive"))
      (node (ref "R18") (pin "2") (pinfunction "2_2") (pintype "passive"))
      (node (ref "U1") (pin "1") (pinfunction "-_1") (pintype "passive"))
    )
    (net (code "5") (name "/CurClt Vsense+") (class "Default")
      (node (ref "P5") (pin "2") (pinfunction "2_2") (pintype "passive"))
      (node (ref "R2") (pin "2") (pinfunction "2_2") (pintype "passive"))
    )
    (net (code "6") (name "/CurCtl Anode") (class "Default")
      (node (ref "J1") (pin "8") (pintype "passive"))
      (node (ref "P3") (pin "1") (pinfunction "1_1") (pintype "passive"))
    )
    (net (code "7") (name "/CurCtl Cathode") (class "Default")
      (node (ref "J1") (pin "7") (pintype "passive"))
      (node (ref "P4") (pin "3") (pinfunction "3_3") (pintype "passive"))
    )
    (net (code "8") (name "/GND_TEC") (class "Default")
      (node (ref "D11") (pin "1") (pinfunction "1_1") (pintype "passive"))
      (node (ref "J2") (pin "7") (pintype "passive"))
      (node (ref "P12") (pin "1") (pinfunction "1_1") (pintype "passive"))
    )
    (net (code "9") (name "/LD-Anode-In") (class "Default")
      (node (ref "C1") (pin "1") (pinfunction "1_1") (pintype "passive"))
      (node (ref "C14") (pin "1") (pinfunction "1_1") (pintype "passive"))
      (node (ref "C15") (pin "1") (pinfunction "1_1") (pintype "passive"))
      (node (ref "C2") (pin "1") (pinfunction "1_1") (pintype "passive"))
      (node (ref "C3") (pin "1") (pinfunction "1_1") (pintype "passive"))
      (node (ref "C4") (pin "1") (pinfunction "1_1") (pintype "passive"))
      (node (ref "L1") (pin "1") (pinfunction "1_1") (pintype "passive"))
      (node (ref "P3") (pin "2") (pinfunction "2_2") (pintype "passive"))
      (node (ref "P5") (pin "1") (pinfunction "1_1") (pintype "passive"))
      (node (ref "P7") (pin "2") (pinfunction "2_2") (pintype "passive"))
      (node (ref "R1") (pin "1") (pinfunction "1_1") (pintype "passive"))
    )
    (net (code "10") (name "/LD-Anode-out") (class "Default")
      (node (ref "D1") (pin "1") (pinfunction "1_1") (pintype "passive"))
      (node (ref "P1") (pin "1") (pinfunction "1_1") (pintype "passive"))
      (node (ref "P7") (pin "3") (pinfunction "3_3") (pintype "passive"))
      (node (ref "R3") (pin "2") (pinfunction "2_2") (pintype "passive"))
      (node (ref "T1") (pin "1") (pinfunction "D_1") (pintype "passive"))
      (node (ref "T2") (pin "1") (pinfunction "D_1") (pintype "passive"))
      (node (ref "T3") (pin "1") (pinfunction "D_1") (pintype "passive"))
      (node (ref "T4") (pin "2") (pinfunction "D_2") (pintype "passive"))
      (node (ref "T5") (pin "2") (pinfunction "D_2") (pintype "passive"))
      (node (ref "T6") (pin "2") (pinfunction "D_2") (pintype "passive"))
    )
    (net (code "11") (name "/LD-Cathode-In") (class "Default")
      (node (ref "C1") (pin "2") (pinfunction "2_2") (pintype "passive"))
      (node (ref "C14") (pin "2") (pinfunction "2_2") (pintype "passive"))
      (node (ref "C15") (pin "2") (pinfunction "2_2") (pintype "passive"))
      (node (ref "C2") (pin "2") (pinfunction "2_2") (pintype "passive"))
      (node (ref "C3") (pin "2") (pinfunction "2_2") (pintype "passive"))
      (node (ref "C4") (pin "2") (pinfunction "2_2") (pintype "passive"))
      (node (ref "L2") (pin "1") (pinfunction "1_1") (pintype "passive"))
      (node (ref "P4") (pin "2") (pinfunction "2_2") (pintype "passive"))
      (node (ref "P5") (pin "3") (pinfunction "3_3") (pintype "passive"))
      (node (ref "P6") (pin "2") (pinfunction "2_2") (pintype "passive"))
      (node (ref "R11") (pin "1") (pinfunction "1_1") (pintype "passive"))
    )
    (net (code "12") (name "/LD-Cathode-out") (class "Default")
      (node (ref "D1") (pin "2") (pinfunction "2_2") (pintype "passive"))
      (node (ref "P2") (pin "1") (pinfunction "1_1") (pintype "passive"))
      (node (ref "P6") (pin "1") (pinfunction "1_1") (pintype "passive"))
      (node (ref "R10") (pin "1") (pinfunction "1_1") (pintype "passive"))
      (node (ref "R12") (pin "2") (pinfunction "2_2") (pintype "passive"))
      (node (ref "R5") (pin "1") (pinfunction "1_1") (pintype "passive"))
      (node (ref "R6") (pin "1") (pinfunction "1_1") (pintype "passive"))
      (node (ref "R7") (pin "1") (pinfunction "1_1") (pintype "passive"))
      (node (ref "R8") (pin "1") (pinfunction "1_1") (pintype "passive"))
      (node (ref "R9") (pin "1") (pinfunction "1_1") (pintype "passive"))
      (node (ref "U2") (pin "5") (pinfunction "+_5") (pintype "passive"))
    )
    (net (code "13") (name "/Led_TEC On+") (class "Default")
      (node (ref "J2") (pin "1") (pintype "passive"))
      (node (ref "P11") (pin "1") (pinfunction "1_1") (pintype "passive"))
      (node (ref "R32") (pin "1") (pinfunction "1_1") (pintype "passive"))
    )
    (net (code "14") (name "/TEC1+") (class "Default")
      (node (ref "J2") (pin "4") (pintype "passive"))
      (node (ref "P15") (pin "1") (pinfunction "1_1") (pintype "passive"))
    )
    (net (code "15") (name "/TEC1-") (class "Default")
      (node (ref "J2") (pin "6") (pintype "passive"))
      (node (ref "P17") (pin "1") (pinfunction "1_1") (pintype "passive"))
    )
    (net (code "16") (name "/TEC2+") (class "Default")
      (node (ref "J2") (pin "5") (pintype "passive"))
      (node (ref "P16") (pin "1") (pinfunction "1_1") (pintype "passive"))
    )
    (net (code "17") (name "/TEC2-") (class "Default")
      (node (ref "J2") (pin "8") (pintype "passive"))
      (node (ref "P18") (pin "1") (pinfunction "1_1") (pintype "passive"))
    )
    (net (code "18") (name "/Th_a") (class "Default")
      (node (ref "J2") (pin "2") (pintype "passive"))
      (node (ref "P13") (pin "1") (pinfunction "1_1") (pintype "passive"))
    )
    (net (code "19") (name "/Th_b") (class "Default")
      (node (ref "J2") (pin "3") (pintype "passive"))
      (node (ref "P14") (pin "1") (pinfunction "1_1") (pintype "passive"))
    )
    (net (code "20") (name "GND") (class "Default")
      (node (ref "C10") (pin "2") (pinfunction "2_2") (pintype "passive"))
      (node (ref "C11") (pin "2") (pinfunction "2_2") (pintype "passive"))
      (node (ref "C12") (pin "2") (pinfunction "2_2") (pintype "passive"))
      (node (ref "C13") (pin "2") (pinfunction "2_2") (pintype "passive"))
      (node (ref "C8") (pin "1") (pinfunction "1_1") (pintype "passive"))
      (node (ref "C9") (pin "1") (pinfunction "1_1") (pintype "passive"))
      (node (ref "D10") (pin "2") (pinfunction "2_2") (pintype "passive"))
      (node (ref "D2") (pin "1") (pinfunction "1_1") (pintype "passive"))
      (node (ref "D3") (pin "1") (pinfunction "1_1") (pintype "passive"))
      (node (ref "D4") (pin "1") (pinfunction "1_1") (pintype "passive"))
      (node (ref "D5") (pin "1") (pinfunction "1_1") (pintype "passive"))
      (node (ref "D6") (pin "1") (pinfunction "A_1") (pintype "passive"))
      (node (ref "D7") (pin "3") (pinfunction "C_3") (pintype "passive"))
      (node (ref "D9") (pin "1") (pinfunction "1_1") (pintype "passive"))
      (node (ref "J1") (pin "3") (pintype "passive"))
      (node (ref "P3") (pin "3") (pinfunction "3_3") (pintype "passive"))
      (node (ref "P4") (pin "1") (pinfunction "1_1") (pintype "passive"))
      (node (ref "R18") (pin "1") (pinfunction "1_1") (pintype "passive"))
      (node (ref "R22") (pin "1") (pinfunction "1_1") (pintype "passive"))
      (node (ref "R25") (pin "1") (pinfunction "1_1") (pintype "passive"))
      (node (ref "R31") (pin "2") (pinfunction "2_2") (pintype "passive"))
      (node (ref "R4") (pin "2") (pinfunction "2_2") (pintype "passive"))
      (node (ref "U1") (pin "6") (pinfunction "-_6") (pintype "passive"))
      (node (ref "U3") (pin "6") (pinfunction "-_6") (pintype "passive"))
      (node (ref "U4") (pin "4") (pinfunction "GND_4") (pintype "passive"))
      (node (ref "U4") (pin "7") (pinfunction "ModSel_7") (pintype "passive"))
    )
    (net (code "21") (name "Net-(C6-Pad1)") (class "Default")
      (node (ref "C6") (pin "1") (pinfunction "1_1") (pintype "passive"))
      (node (ref "R13") (pin "2") (pinfunction "2_2") (pintype "passive"))
      (node (ref "U1") (pin "4") (pinfunction "-_4") (pintype "passive"))
    )
    (net (code "22") (name "Net-(C7-Pad1)") (class "Default")
      (node (ref "C7") (pin "1") (pinfunction "1_1") (pintype "passive"))
      (node (ref "TP4") (pin "1") (pinfunction "1_1") (pintype "passive"))
      (node (ref "U3") (pin "7") (pinfunction "-_7") (pintype "passive"))
    )
    (net (code "23") (name "Net-(C7-Pad2)") (class "Default")
      (node (ref "C7") (pin "2") (pinfunction "2_2") (pintype "passive"))
      (node (ref "R20") (pin "1") (pinfunction "1_1") (pintype "passive"))
    )
    (net (code "24") (name "Net-(C13-Pad1)") (class "Default")
      (node (ref "C13") (pin "1") (pinfunction "1_1") (pintype "passive"))
      (node (ref "R30") (pin "1") (pinfunction "1_1") (pintype "passive"))
    )
    (net (code "25") (name "Net-(D3-Pad2)") (class "Default")
      (node (ref "D3") (pin "2") (pinfunction "2_2") (pintype "passive"))
      (node (ref "P8") (pin "1") (pinfunction "1_1") (pintype "passive"))
      (node (ref "R13") (pin "1") (pinfunction "1_1") (pintype "passive"))
      (node (ref "R15") (pin "2") (pinfunction "2_2") (pintype "passive"))
    )
    (net (code "26") (name "Net-(D5-Pad2)") (class "Default")
      (node (ref "D5") (pin "2") (pinfunction "2_2") (pintype "passive"))
      (node (ref "P9") (pin "1") (pinfunction "1_1") (pintype "passive"))
      (node (ref "R24") (pin "2") (pinfunction "2_2") (pintype "passive"))
      (node (ref "U3") (pin "4") (pinfunction "-_4") (pintype "passive"))
    )
    (net (code "27") (name "Net-(D8-Pad2)") (class "Default")
      (node (ref "D8") (pin "2") (pinfunction "2_2") (pintype "passive"))
      (node (ref "R26") (pin "2") (pinfunction "2_2") (pintype "passive"))
    )
    (net (code "28") (name "Net-(D11-Pad2)") (class "Default")
      (node (ref "D11") (pin "2") (pinfunction "2_2") (pintype "passive"))
      (node (ref "R32") (pin "2") (pinfunction "2_2") (pintype "passive"))
    )
    (net (code "29") (name "Net-(J1-Pad6)") (class "Default")
      (node (ref "J1") (pin "6") (pintype "passive"))
      (node (ref "R4") (pin "1") (pinfunction "1_1") (pintype "passive"))
    )
    (net (code "30") (name "Net-(J1-Pad9)") (class "Default")
      (node (ref "J1") (pin "9") (pintype "passive"))
      (node (ref "R2") (pin "1") (pinfunction "1_1") (pintype "passive"))
    )
    (net (code "31") (name "Net-(L1-Pad2)") (class "Default")
      (node (ref "L1") (pin "2") (pinfunction "2_2") (pintype "passive"))
      (node (ref "R1") (pin "2") (pinfunction "2_2") (pintype "passive"))
      (node (ref "R3") (pin "1") (pinfunction "1_1") (pintype "passive"))
    )
    (net (code "32") (name "Net-(L2-Pad2)") (class "Default")
      (node (ref "L2") (pin "2") (pinfunction "2_2") (pintype "passive"))
      (node (ref "R11") (pin "2") (pinfunction "2_2") (pintype "passive"))
      (node (ref "R12") (pin "1") (pinfunction "1_1") (pintype "passive"))
    )
    (net (code "33") (name "Net-(P10-Pad1)") (class "Default")
      (node (ref "P10") (pin "1") (pinfunction "1_1") (pintype "passive"))
      (node (ref "R29") (pin "1") (pinfunction "1_1") (pintype "passive"))
    )
    (net (code "34") (name "Net-(R14-Pad1)") (class "Default")
      (node (ref "R14") (pin "1") (pinfunction "1_1") (pintype "passive"))
      (node (ref "U1") (pin "2") (pinfunction "Rg_2") (pintype "passive"))
    )
    (net (code "35") (name "Net-(R14-Pad2)") (class "Default")
      (node (ref "R14") (pin "2") (pinfunction "2_2") (pintype "passive"))
      (node (ref "U1") (pin "3") (pinfunction "Rg_3") (pintype "passive"))
    )
    (net (code "36") (name "Net-(R17-Pad1)") (class "Default")
      (node (ref "R17") (pin "1") (pinfunction "1_1") (pintype "passive"))
      (node (ref "TP1") (pin "1") (pinfunction "1_1") (pintype "passive"))
      (node (ref "U1") (pin "7") (pinfunction "-_7") (pintype "passive"))
    )
    (net (code "37") (name "Net-(R19-Pad1)") (class "Default")
      (node (ref "R19") (pin "1") (pinfunction "1_1") (pintype "passive"))
      (node (ref "R20") (pin "2") (pinfunction "2_2") (pintype "passive"))
      (node (ref "R20") (pin "3") (pinfunction "3_3") (pintype "passive"))
    )
    (net (code "38") (name "Net-(R23-Pad1)") (class "Default")
      (node (ref "R23") (pin "1") (pinfunction "1_1") (pintype "passive"))
      (node (ref "U3") (pin "2") (pinfunction "Rg_2") (pintype "passive"))
    )
    (net (code "39") (name "Net-(R23-Pad2)") (class "Default")
      (node (ref "R23") (pin "2") (pinfunction "2_2") (pintype "passive"))
      (node (ref "U3") (pin "3") (pinfunction "Rg_3") (pintype "passive"))
    )
    (net (code "40") (name "Net-(T1-G)") (class "Default")
      (node (ref "C5") (pin "2") (pinfunction "2_2") (pintype "passive"))
      (node (ref "R16") (pin "2") (pinfunction "2_2") (pintype "passive"))
      (node (ref "R27") (pin "1") (pinfunction "1_1") (pintype "passive"))
      (node (ref "T1") (pin "3") (pinfunction "G_3") (pintype "passive"))
      (node (ref "T2") (pin "3") (pinfunction "G_3") (pintype "passive"))
      (node (ref "T3") (pin "3") (pinfunction "G_3") (pintype "passive"))
      (node (ref "T4") (pin "3") (pinfunction "G_3") (pintype "passive"))
      (node (ref "T5") (pin "3") (pinfunction "G_3") (pintype "passive"))
      (node (ref "T6") (pin "3") (pinfunction "G_3") (pintype "passive"))
      (node (ref "TP2") (pin "1") (pinfunction "1_1") (pintype "passive"))
      (node (ref "U2") (pin "1") (pinfunction "OUT_1") (pintype "passive"))
    )
    (net (code "41") (name "Net-(T1-S)") (class "Default")
      (node (ref "R5") (pin "2") (pinfunction "2_2") (pintype "passive"))
      (node (ref "T1") (pin "2") (pinfunction "S_2") (pintype "passive"))
    )
    (net (code "42") (name "Net-(T2-S)") (class "Default")
      (node (ref "R6") (pin "2") (pinfunction "2_2") (pintype "passive"))
      (node (ref "T2") (pin "2") (pinfunction "S_2") (pintype "passive"))
    )
    (net (code "43") (name "Net-(T3-S)") (class "Default")
      (node (ref "R7") (pin "2") (pinfunction "2_2") (pintype "passive"))
      (node (ref "T3") (pin "2") (pinfunction "S_2") (pintype "passive"))
    )
    (net (code "44") (name "Net-(T4-S)") (class "Default")
      (node (ref "R8") (pin "2") (pinfunction "2_2") (pintype "passive"))
      (node (ref "T4") (pin "1") (pinfunction "S_1") (pintype "passive"))
    )
    (net (code "45") (name "Net-(T5-S)") (class "Default")
      (node (ref "R9") (pin "2") (pinfunction "2_2") (pintype "passive"))
      (node (ref "T5") (pin "1") (pinfunction "S_1") (pintype "passive"))
    )
    (net (code "46") (name "Net-(T6-S)") (class "Default")
      (node (ref "R10") (pin "2") (pinfunction "2_2") (pintype "passive"))
      (node (ref "T6") (pin "1") (pinfunction "S_1") (pintype "passive"))
    )
    (net (code "47") (name "Net-(U2A-+)") (class "Default")
      (node (ref "R21") (pin "2") (pinfunction "2_2") (pintype "passive"))
      (node (ref "R22") (pin "2") (pinfunction "2_2") (pintype "passive"))
      (node (ref "TP3") (pin "1") (pinfunction "1_1") (pintype "passive"))
      (node (ref "U2") (pin "3") (pinfunction "+_3") (pintype "passive"))
    )
    (net (code "48") (name "Net-(U2A--)") (class "Default")
      (node (ref "C5") (pin "1") (pinfunction "1_1") (pintype "passive"))
      (node (ref "R16") (pin "1") (pinfunction "1_1") (pintype "passive"))
      (node (ref "R17") (pin "2") (pinfunction "2_2") (pintype "passive"))
      (node (ref "R19") (pin "2") (pinfunction "2_2") (pintype "passive"))
      (node (ref "U2") (pin "2") (pinfunction "-_2") (pintype "passive"))
    )
    (net (code "49") (name "Net-(U2B--)") (class "Default")
      (node (ref "R21") (pin "1") (pinfunction "1_1") (pintype "passive"))
      (node (ref "U2") (pin "6") (pinfunction "-_6") (pintype "passive"))
      (node (ref "U2") (pin "7") (pinfunction "OUT_7") (pintype "passive"))
    )
    (net (code "50") (name "Net-(U4-In1)") (class "Default")
      (node (ref "R27") (pin "2") (pinfunction "2_2") (pintype "passive"))
      (node (ref "R28") (pin "1") (pinfunction "1_1") (pintype "passive"))
      (node (ref "U4") (pin "2") (pinfunction "In1_2") (pintype "passive"))
    )
    (net (code "51") (name "Net-(U4-In2)") (class "Default")
      (node (ref "R28") (pin "2") (pinfunction "2_2") (pintype "passive"))
      (node (ref "R29") (pin "2") (pinfunction "2_2") (pintype "passive"))
      (node (ref "R31") (pin "1") (pinfunction "1_1") (pintype "passive"))
      (node (ref "U4") (pin "1") (pinfunction "Vref_1") (pintype "passive"))
      (node (ref "U4") (pin "3") (pinfunction "In2_3") (pintype "passive"))
    )
    (net (code "52") (name "Net-(U4-Out1)") (class "Default")
      (node (ref "D8") (pin "1") (pinfunction "1_1") (pintype "passive"))
      (node (ref "R30") (pin "2") (pinfunction "2_2") (pintype "passive"))
      (node (ref "U4") (pin "5") (pinfunction "Out2_5") (pintype "passive"))
      (node (ref "U4") (pin "6") (pinfunction "Out1_6") (pintype "passive"))
    )
    (net (code "53") (name "unconnected-(J1-Pad2)") (class "Default")
      (node (ref "J1") (pin "2") (pintype "passive"))
    )
    (net (code "54") (name "unconnected-(J1-Pad4)") (class "Default")
      (node (ref "J1") (pin "4") (pintype "passive"))
    )
    (net (code "55") (name "unconnected-(J1-PadM1)") (class "Default")
      (node (ref "J1") (pin "M1") (pintype "passive"))
    )
    (net (code "56") (name "unconnected-(J1-PadM2)") (class "Default")
      (node (ref "J1") (pin "M2") (pintype "passive"))
    )
    (net (code "57") (name "unconnected-(J2-Pad9)") (class "Default")
      (node (ref "J2") (pin "9") (pintype "passive"))
    )
    (net (code "58") (name "unconnected-(J2-PadM1)") (class "Default")
      (node (ref "J2") (pin "M1") (pintype "passive"))
    )
    (net (code "59") (name "unconnected-(J2-PadM2)") (class "Default")
      (node (ref "J2") (pin "M2") (pintype "passive"))
    )
    (net (code "60") (name "unconnected-(P6-Pad3)") (class "Default")
      (node (ref "P6") (pin "3") (pinfunction "3_3") (pintype "passive"))
    )
    (net (code "61") (name "unconnected-(P7-Pad1)") (class "Default")
      (node (ref "P7") (pin "1") (pinfunction "1_1") (pintype "passive"))
    )
  )
)
